# LDO_3v3_LM2937.net
KiCad netlist of a schematic drawn in Altium Designer
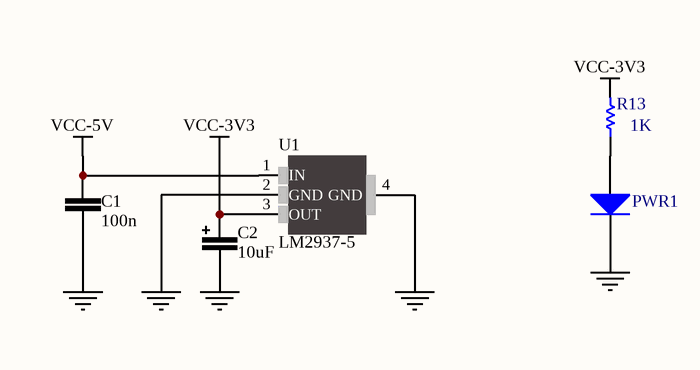
[diagram p0: LDO_3v3_LM2937.SchDoc]

(export (version "E")
  (design (tool "Eeschema 10.0.6"))
  (components
    (comp (ref "C1")
      (value "100n")
      (footprint "CER_0603")
      (description "CAP CER 100n 10V X5R 10% 0603")
      (libsource (lib "Capacitors") (part "06032105"))
    )
    (comp (ref "C2")
      (value "10uF")
      (footprint "TANT_1210")
      (description "CAP TANT 10u")
      (libsource (lib "Capacitors") (part "00001106"))
    )
    (comp (ref "PWR1")
      (value "~")
      (footprint "SMC")
      (description "Default Diode")
      (fields (field (name "PUBLISHER") "Altium Limited"))
      (libsource (lib "Miscellaneous Devices") (part "Diode"))
    )
    (comp (ref "R13")
      (value "1K")
      (footprint "AXIAL-0.3")
      (description "Resistor")
      (fields (field (name "PUBLISHER") "Altium Limited"))
      (libsource (lib "Miscellaneous Devices") (part "Res1"))
    )
    (comp (ref "U1")
      (value "LM2937-5")
      (footprint "SOT223")
      (description "IC REG LINEAR 5V 400MA SOT223-4")
      (libsource (lib "Integrated_circuits") (part "00000007"))
    )
  )
  (nets
    (net (code "1") (name "GND") (class "Default")
      (node (ref "C1") (pin "1") (pinfunction "1_1") (pintype "passive"))
      (node (ref "C2") (pin "2") (pinfunction "2_2") (pintype "passive"))
      (node (ref "PWR1") (pin "2") (pinfunction "K_2") (pintype "passive"))
      (node (ref "U1") (pin "2") (pinfunction "GND_2") (pintype "passive"))
      (node (ref "U1") (pin "4") (pinfunction "GND_4") (pintype "passive"))
    )
    (net (code "2") (name "Net-(PWR1-A)") (class "Default")
      (node (ref "PWR1") (pin "1") (pinfunction "A_1") (pintype "passive"))
      (node (ref "R13") (pin "1") (pinfunction "1_1") (pintype "passive"))
    )
    (net (code "3") (name "VCC-3V3") (class "Default")
      (node (ref "C2") (pin "1") (pinfunction "1_1") (pintype "passive"))
      (node (ref "U1") (pin "3") (pinfunction "OUT_3") (pintype "passive"))
    )
    (net (code "4") (name "VCC-5V") (class "Default")
      (node (ref "C1") (pin "2") (pinfunction "2_2") (pintype "passive"))
      (node (ref "U1") (pin "1") (pinfunction "IN_1") (pintype "passive"))
    )
    (net (code "5") (name "unconnected-(R13-Pad2)") (class "Default")
      (node (ref "R13") (pin "2") (pinfunction "2_2") (pintype "passive"))
    )
  )
)
